# RADG-Power-S03-V00.net
KiCad netlist of a schematic drawn in Altium Designer
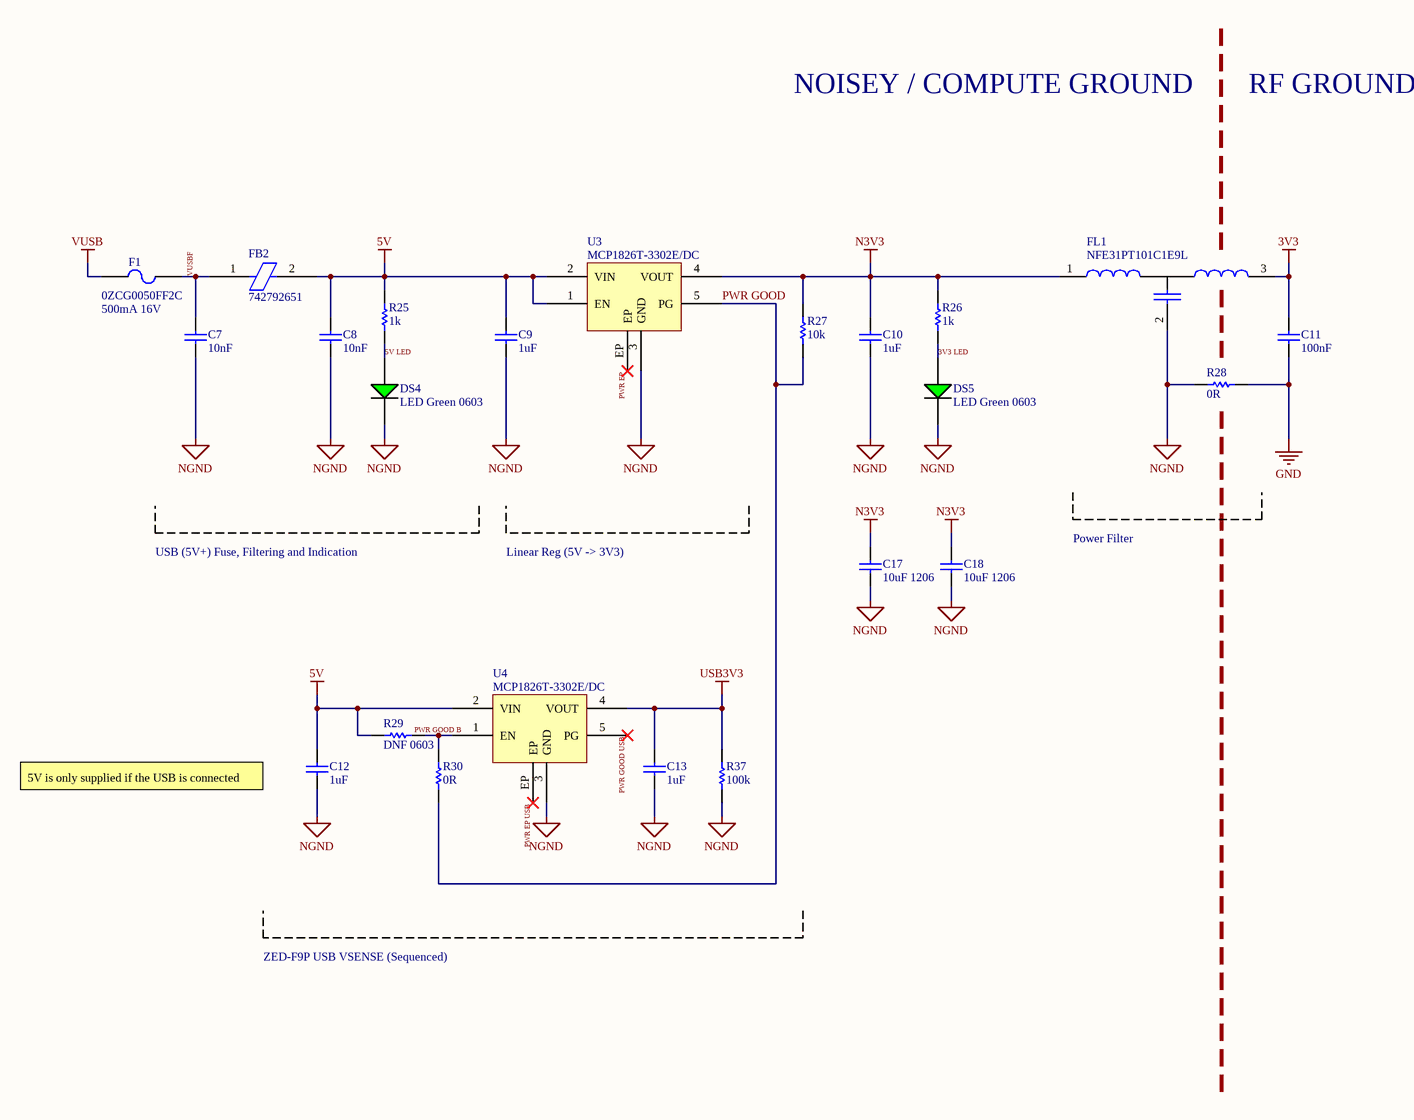
[diagram p0: RADG-Power-S03-V00.SchDoc]

(export (version "E")
  (design (tool "Eeschema 10.0.6"))
  (components
    (comp (ref "C7")
      (value "10nF")
      (footprint "Cap_Ceramic_0603")
      (description "Capacitor, Ceramic, SMD, 10nF, 50V, 5%, X7R, 0603")
      (libsource (lib "StandardCapacitors") (part "10nF 50V 5% X7R 0603"))
    )
    (comp (ref "C8")
      (value "10nF")
      (footprint "Cap_Ceramic_0603")
      (description "Capacitor, Ceramic, SMD, 10nF, 50V, 5%, X7R, 0603")
      (libsource (lib "StandardCapacitors") (part "10nF 50V 5% X7R 0603"))
    )
    (comp (ref "C9")
      (value "1uF")
      (footprint "Cap_Ceramic_0603")
      (description "Capacitor, Ceramic, SMD, 1uF, 25V, 5%, X7R, 0603")
      (libsource (lib "StandardCapacitors") (part "1uF 25V 5% X7R 0603"))
    )
    (comp (ref "C10")
      (value "1uF")
      (footprint "Cap_Ceramic_0603")
      (description "Capacitor, Ceramic, SMD, 1uF, 25V, 5%, X7R, 0603")
      (libsource (lib "StandardCapacitors") (part "1uF 25V 5% X7R 0603"))
    )
    (comp (ref "C11")
      (value "100nF")
      (footprint "Cap_Ceramic_0603")
      (description "Capacitor, Ceramic, SMD, 100nF, 50V, 5%, X7R, 0603")
      (libsource (lib "StandardCapacitors") (part "100nF 50V 5% X7R 0603"))
    )
    (comp (ref "C12")
      (value "1uF")
      (footprint "Cap_Ceramic_0603")
      (description "Capacitor, Ceramic, SMD, 1uF, 25V, 5%, X7R, 0603")
      (libsource (lib "StandardCapacitors") (part "1uF 25V 5% X7R 0603"))
    )
    (comp (ref "C13")
      (value "1uF")
      (footprint "Cap_Ceramic_0603")
      (description "Capacitor, Ceramic, SMD, 1uF, 25V, 5%, X7R, 0603")
      (libsource (lib "StandardCapacitors") (part "1uF 25V 5% X7R 0603"))
    )
    (comp (ref "C17")
      (value "10uF 1206")
      (footprint "Cap_Ceramic_1206")
      (description "Capacitor, Ceramic, SMD, 10uF, 25V, 10%, X7R, 1206")
      (libsource (lib "StandardCapacitors") (part "10uF 25V 10% X7R 1206"))
    )
    (comp (ref "C18")
      (value "10uF 1206")
      (footprint "Cap_Ceramic_1206")
      (description "Capacitor, Ceramic, SMD, 10uF, 25V, 10%, X7R, 1206")
      (libsource (lib "StandardCapacitors") (part "10uF 25V 10% X7R 1206"))
    )
    (comp (ref "DS4")
      (value "LED Green 0603")
      (footprint "LED GREEN 0603")
      (libsource (lib "QUTMS_LEDLibrary") (part "LED Green 0603"))
    )
    (comp (ref "DS5")
      (value "LED Green 0603")
      (footprint "LED GREEN 0603")
      (libsource (lib "QUTMS_LEDLibrary") (part "LED Green 0603"))
    )
    (comp (ref "F1")
      (value "0ZCG0050FF2C")
      (footprint "1812 FUSE")
      (description "Polymeric PTC Resettable Fuse 16V 500mA Ih Surface Mount 1812 (4532 Metric), Concave")
      (libsource (lib "QUTMS_FuseLibrary") (part "0ZCG0050FF2C"))
    )
    (comp (ref "FB2")
      (value "742792651")
      (footprint "Inductor_0603")
      (description "600 Ohms @ 100MHz 1 Signal Line Ferrite Bead 0603 (1608 Metric) 1A 200mOhm")
      (libsource (lib "QUTMS_InductorLibrary") (part "742792651"))
    )
    (comp (ref "FL1")
      (value "NFE31PT101C1E9L")
      (footprint "NFE31PT101C1E9L")
      (description "LC (T-Type) EMI Filter 3rd Order Low Pass 1 Channel C = 100pF 6A 1206 (3216 Metric), 3 PC Pad")
      (libsource (lib "QUTMS_PowerSupplyLibrary") (part "NFE31PT101C1E9L"))
    )
    (comp (ref "R25")
      (value "1k")
      (footprint "Res_ThinFilm_0603")
      (description "Resistor, SMD, 1k, 0.1W, 5%, 0603")
      (libsource (lib "StandardResistors") (part "1k 5% 0603"))
    )
    (comp (ref "R26")
      (value "1k")
      (footprint "Res_ThinFilm_0603")
      (description "Resistor, SMD, 1k, 0.1W, 5%, 0603")
      (libsource (lib "StandardResistors") (part "1k 5% 0603"))
    )
    (comp (ref "R27")
      (value "10k")
      (footprint "Res_ThinFilm_0603")
      (description "Resistor, SMD, 10k, 0.1W, 5%, 0603")
      (libsource (lib "StandardResistors") (part "10k 5% 0603"))
    )
    (comp (ref "R28")
      (value "0R")
      (footprint "Res_ThinFilm_0603")
      (description "Resistor, SMD, 0R, 0.1W, 5%, 0603")
      (libsource (lib "StandardResistors") (part "0R 5% 0603"))
    )
    (comp (ref "R29")
      (value "DNF 0603")
      (footprint "Res_ThinFilm_0603")
      (description "Resistor, SMD, DNF, 0.1W, 0603")
      (libsource (lib "StandardResistors") (part "DNF 0603"))
    )
    (comp (ref "R30")
      (value "0R")
      (footprint "Res_ThinFilm_0603")
      (description "Resistor, SMD, 0R, 0.1W, 5%, 0603")
      (libsource (lib "StandardResistors") (part "0R 5% 0603"))
    )
    (comp (ref "R37")
      (value "100k")
      (footprint "Res_ThinFilm_0603")
      (description "Resistor, SMD, 100k, 0.1W, 5%, 0603")
      (libsource (lib "StandardResistors") (part "100k 5%, 0603"))
    )
    (comp (ref "U3")
      (value "MCP1826T-3302E/DC")
      (footprint "SOT-223-5")
      (description "Linear Voltage Regulator IC Positive Fixed 1 Output 1A SOT-223-5")
      (libsource (lib "QUTMS_PowerSupplyLibrary") (part "MCP1826T-3302E/DC"))
    )
    (comp (ref "U4")
      (value "MCP1826T-3302E/DC")
      (footprint "SOT-223-5")
      (description "Linear Voltage Regulator IC Positive Fixed 1 Output 1A SOT-223-5")
      (libsource (lib "QUTMS_PowerSupplyLibrary") (part "MCP1826T-3302E/DC"))
    )
  )
  (nets
    (net (code "1") (name "/3V3 LED") (class "Default")
      (node (ref "DS5") (pin "1") (pinfunction "A_1") (pintype "passive"))
      (node (ref "R26") (pin "1") (pinfunction "1_1") (pintype "passive"))
    )
    (net (code "2") (name "/5V LED") (class "Default")
      (node (ref "DS4") (pin "1") (pinfunction "A_1") (pintype "passive"))
      (node (ref "R25") (pin "1") (pinfunction "1_1") (pintype "passive"))
    )
    (net (code "3") (name "/PWR EP") (class "Default")
      (node (ref "U3") (pin "EP") (pinfunction "EP_EP") (pintype "passive+no_connect"))
    )
    (net (code "4") (name "/PWR EP USB") (class "Default")
      (node (ref "U4") (pin "EP") (pinfunction "EP_EP") (pintype "passive+no_connect"))
    )
    (net (code "5") (name "/PWR GOOD") (class "Default")
      (node (ref "R27") (pin "1") (pinfunction "1_1") (pintype "passive"))
      (node (ref "R30") (pin "1") (pinfunction "1_1") (pintype "passive"))
      (node (ref "U3") (pin "5") (pinfunction "PG_5") (pintype "passive"))
    )
    (net (code "6") (name "/PWR GOOD B") (class "Default")
      (node (ref "R29") (pin "2") (pinfunction "2_2") (pintype "passive"))
      (node (ref "R30") (pin "2") (pinfunction "2_2") (pintype "passive"))
      (node (ref "U4") (pin "1") (pinfunction "EN_1") (pintype "passive"))
    )
    (net (code "7") (name "/PWR GOOD USB") (class "Default")
      (node (ref "U4") (pin "5") (pinfunction "PG_5") (pintype "passive+no_connect"))
    )
    (net (code "8") (name "/VUSBF") (class "Default")
      (node (ref "C7") (pin "2") (pinfunction "2_2") (pintype "passive"))
      (node (ref "F1") (pin "2") (pinfunction "2_2") (pintype "passive"))
      (node (ref "FB2") (pin "1") (pinfunction "1_1") (pintype "passive"))
    )
    (net (code "9") (name "3V3") (class "Default")
      (node (ref "C11") (pin "2") (pinfunction "2_2") (pintype "passive"))
      (node (ref "FL1") (pin "3") (pinfunction "3_3") (pintype "passive"))
    )
    (net (code "10") (name "5V") (class "Default")
      (node (ref "C12") (pin "2") (pinfunction "2_2") (pintype "passive"))
      (node (ref "C8") (pin "2") (pinfunction "2_2") (pintype "passive"))
      (node (ref "C9") (pin "2") (pinfunction "2_2") (pintype "passive"))
      (node (ref "FB2") (pin "2") (pinfunction "2_2") (pintype "passive"))
      (node (ref "R25") (pin "2") (pinfunction "2_2") (pintype "passive"))
      (node (ref "R29") (pin "1") (pinfunction "1_1") (pintype "passive"))
      (node (ref "U3") (pin "1") (pinfunction "EN_1") (pintype "passive"))
      (node (ref "U3") (pin "2") (pinfunction "VIN_2") (pintype "passive"))
      (node (ref "U4") (pin "2") (pinfunction "VIN_2") (pintype "passive"))
    )
    (net (code "11") (name "GND") (class "Default")
      (node (ref "C11") (pin "1") (pinfunction "1_1") (pintype "passive"))
      (node (ref "R28") (pin "2") (pinfunction "2_2") (pintype "passive"))
    )
    (net (code "12") (name "N3V3") (class "Default")
      (node (ref "C10") (pin "2") (pinfunction "2_2") (pintype "passive"))
      (node (ref "C17") (pin "2") (pinfunction "2_2") (pintype "passive"))
      (node (ref "C18") (pin "2") (pinfunction "2_2") (pintype "passive"))
      (node (ref "FL1") (pin "1") (pinfunction "1_1") (pintype "passive"))
      (node (ref "R26") (pin "2") (pinfunction "2_2") (pintype "passive"))
      (node (ref "R27") (pin "2") (pinfunction "2_2") (pintype "passive"))
      (node (ref "U3") (pin "4") (pinfunction "VOUT_4") (pintype "passive"))
    )
    (net (code "13") (name "NGND") (class "Default")
      (node (ref "C10") (pin "1") (pinfunction "1_1") (pintype "passive"))
      (node (ref "C12") (pin "1") (pinfunction "1_1") (pintype "passive"))
      (node (ref "C13") (pin "1") (pinfunction "1_1") (pintype "passive"))
      (node (ref "C17") (pin "1") (pinfunction "1_1") (pintype "passive"))
      (node (ref "C18") (pin "1") (pinfunction "1_1") (pintype "passive"))
      (node (ref "C7") (pin "1") (pinfunction "1_1") (pintype "passive"))
      (node (ref "C8") (pin "1") (pinfunction "1_1") (pintype "passive"))
      (node (ref "C9") (pin "1") (pinfunction "1_1") (pintype "passive"))
      (node (ref "DS4") (pin "2") (pinfunction "C_2") (pintype "passive"))
      (node (ref "DS5") (pin "2") (pinfunction "C_2") (pintype "passive"))
      (node (ref "FL1") (pin "2") (pinfunction "2_2") (pintype "passive"))
      (node (ref "R28") (pin "1") (pinfunction "1_1") (pintype "passive"))
      (node (ref "R37") (pin "1") (pinfunction "1_1") (pintype "passive"))
      (node (ref "U3") (pin "3") (pinfunction "GND_3") (pintype "passive"))
      (node (ref "U4") (pin "3") (pinfunction "GND_3") (pintype "passive"))
    )
    (net (code "14") (name "USB3V3") (class "Default")
      (node (ref "C13") (pin "2") (pinfunction "2_2") (pintype "passive"))
      (node (ref "R37") (pin "2") (pinfunction "2_2") (pintype "passive"))
      (node (ref "U4") (pin "4") (pinfunction "VOUT_4") (pintype "passive"))
    )
    (net (code "15") (name "VUSB") (class "Default")
      (node (ref "F1") (pin "1") (pinfunction "1_1") (pintype "passive"))
    )
  )
)
